# adcfft.net
KiCad netlist of a schematic drawn in EAGLE
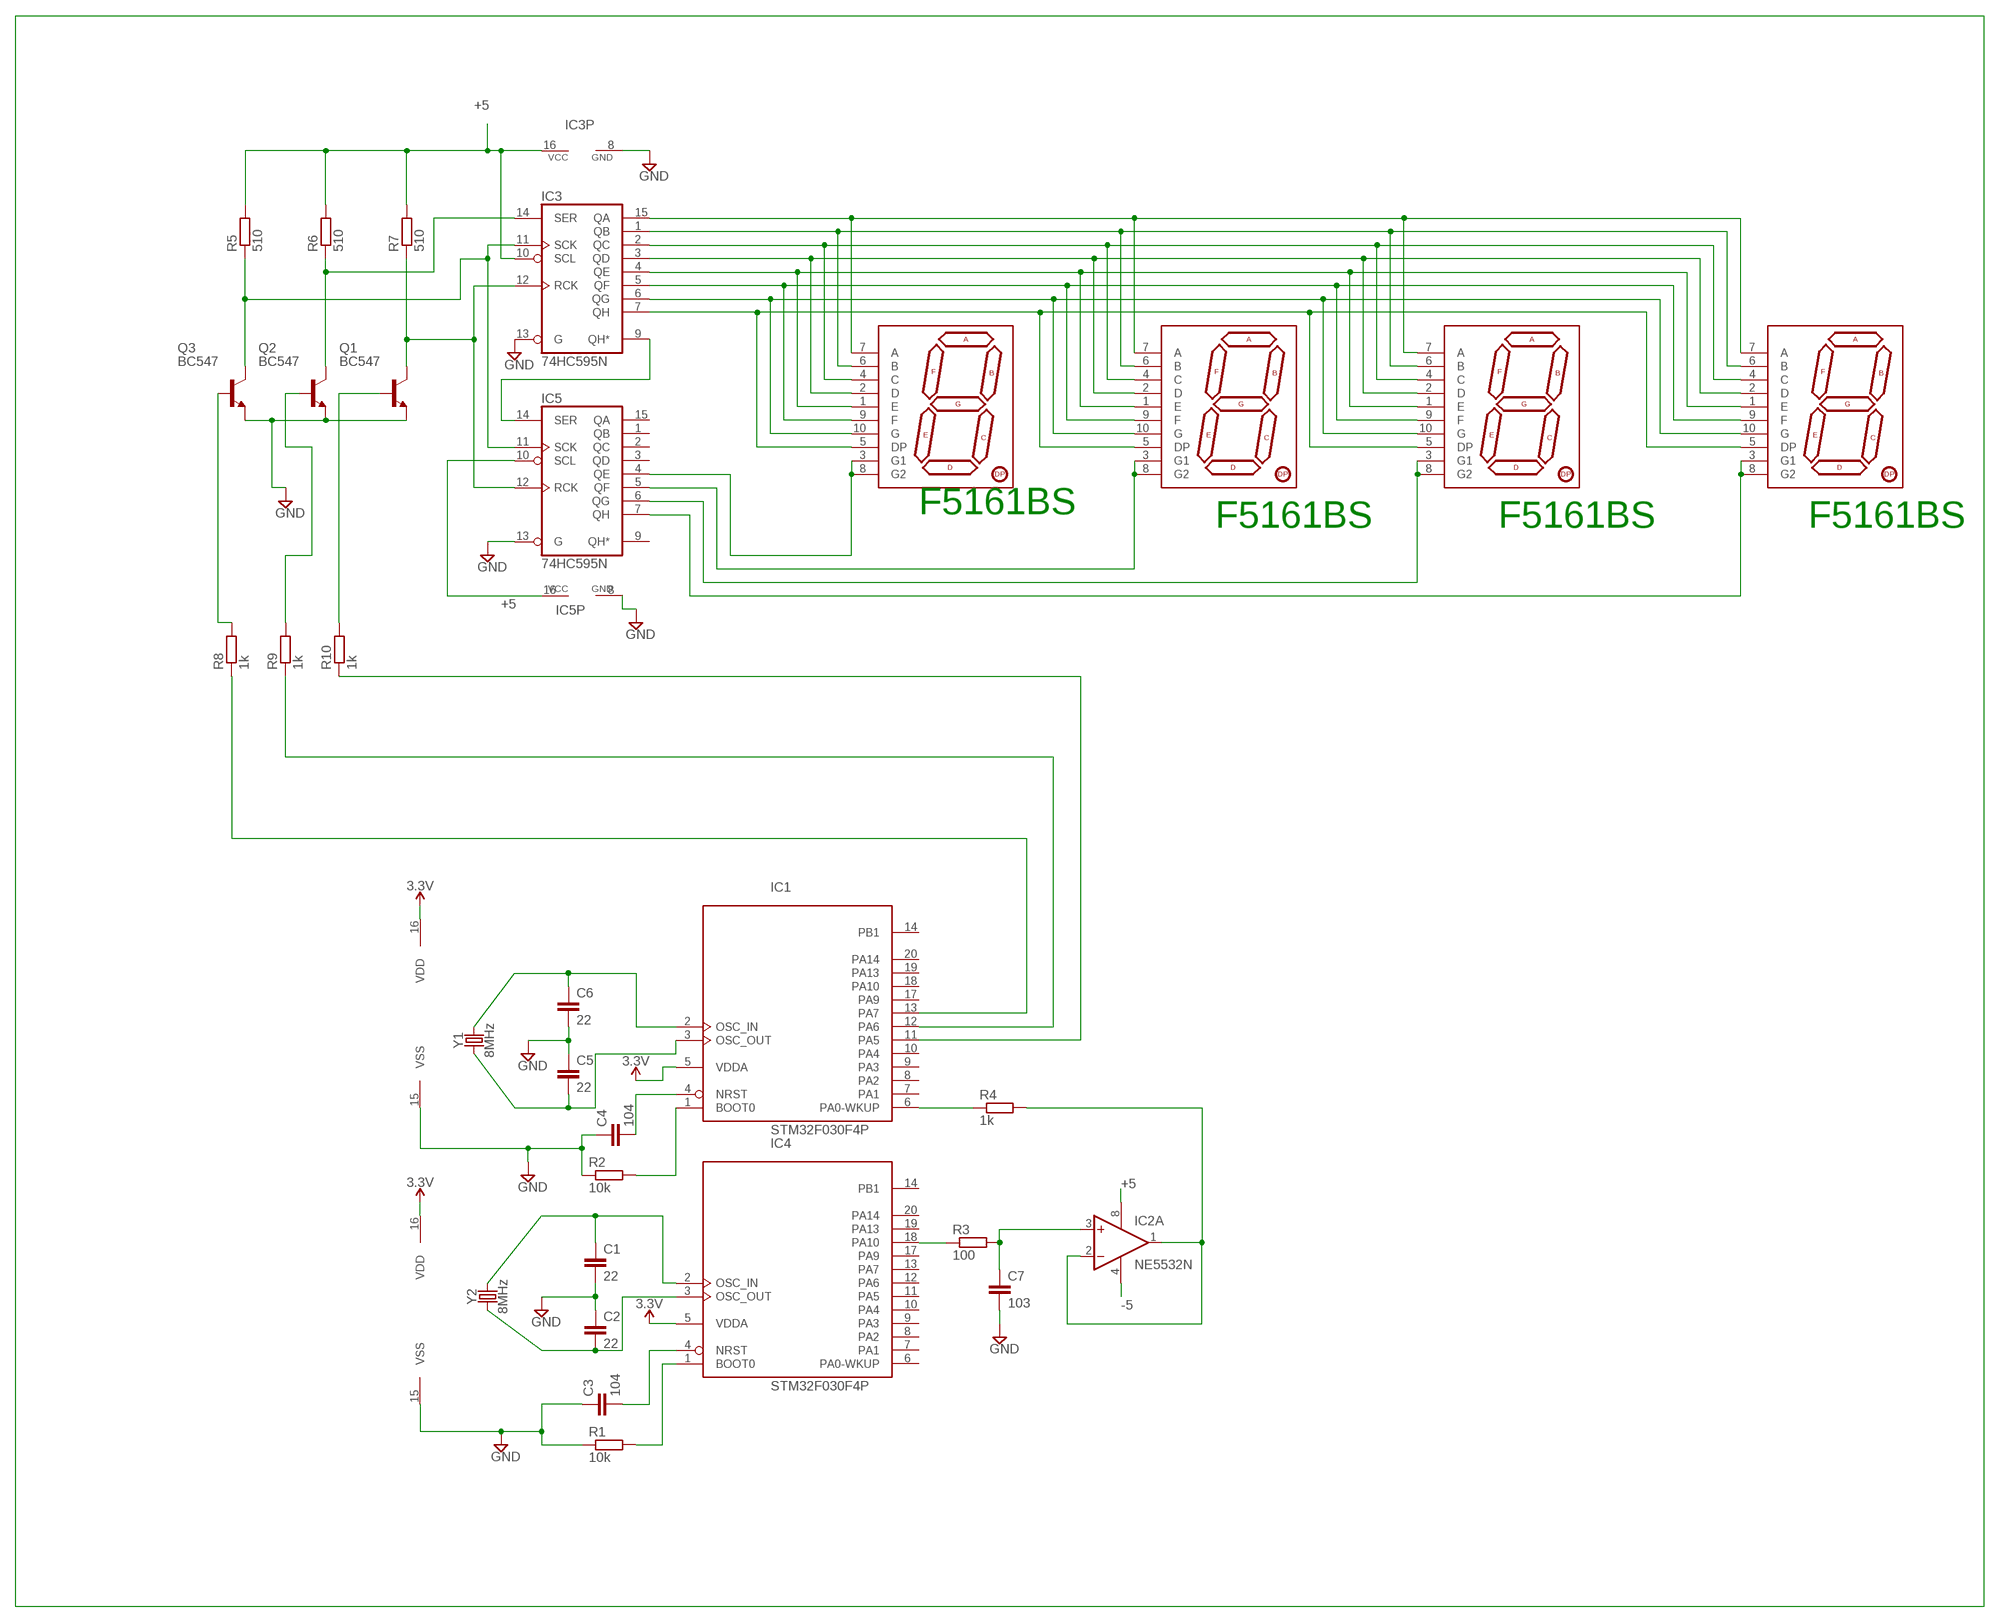
[diagram p0: schematic, sheet 1]

(export (version "E")
  (design (tool "Eeschema 10.0.6"))
  (components
    (comp (ref "C1")
      (value "22")
      (footprint "eagle-import:C0504")
      (libsource (lib "eagle-import") (part "C-EUC0504"))
    )
    (comp (ref "C2")
      (value "22")
      (footprint "eagle-import:C0504")
      (libsource (lib "eagle-import") (part "C-EUC0504"))
    )
    (comp (ref "C3")
      (value "104")
      (footprint "eagle-import:C0504")
      (libsource (lib "eagle-import") (part "C-EUC0504"))
    )
    (comp (ref "C4")
      (value "104")
      (footprint "eagle-import:C0504")
      (libsource (lib "eagle-import") (part "C-EUC0504"))
    )
    (comp (ref "C5")
      (value "22")
      (footprint "eagle-import:C0504")
      (libsource (lib "eagle-import") (part "C-EUC0504"))
    )
    (comp (ref "C6")
      (value "22")
      (footprint "eagle-import:C0504")
      (libsource (lib "eagle-import") (part "C-EUC0504"))
    )
    (comp (ref "C7")
      (value "103")
      (footprint "eagle-import:C0504")
      (libsource (lib "eagle-import") (part "C-EUC0504"))
    )
    (comp (ref "IC1")
      (value "STM32F030F4P")
      (footprint "eagle-import:TSSOP20-I")
      (libsource (lib "eagle-import") (part "STM32F030FP4"))
    )
    (comp (ref "IC2")
      (value "NE5532N")
      (footprint "eagle-import:DIL08")
      (libsource (lib "eagle-import") (part "NE5532N"))
    )
    (comp (ref "IC3")
      (value "74HC595N")
      (footprint "eagle-import:DIL16")
      (libsource (lib "eagle-import") (part "74595NHC"))
    )
    (comp (ref "IC4")
      (value "STM32F030F4P")
      (footprint "eagle-import:TSSOP20-I")
      (libsource (lib "eagle-import") (part "STM32F030FP4"))
    )
    (comp (ref "IC5")
      (value "74HC595N")
      (footprint "eagle-import:DIL16")
      (libsource (lib "eagle-import") (part "74595NHC"))
    )
    (comp (ref "Q1")
      (value "BC547")
      (footprint "eagle-import:TO92")
      (libsource (lib "eagle-import") (part "BC547"))
    )
    (comp (ref "Q2")
      (value "BC547")
      (footprint "eagle-import:TO92")
      (libsource (lib "eagle-import") (part "BC547"))
    )
    (comp (ref "Q3")
      (value "BC547")
      (footprint "eagle-import:TO92")
      (libsource (lib "eagle-import") (part "BC547"))
    )
    (comp (ref "R1")
      (value "10k")
      (footprint "eagle-import:0207_10")
      (libsource (lib "eagle-import") (part "R-EU_0207/10"))
    )
    (comp (ref "R2")
      (value "10k")
      (footprint "eagle-import:0207_10")
      (libsource (lib "eagle-import") (part "R-EU_0207/10"))
    )
    (comp (ref "R3")
      (value "100")
      (footprint "eagle-import:0207_10")
      (libsource (lib "eagle-import") (part "R-EU_0207/10"))
    )
    (comp (ref "R4")
      (value "1k")
      (footprint "eagle-import:0207_10")
      (libsource (lib "eagle-import") (part "R-EU_0207/10"))
    )
    (comp (ref "R5")
      (value "510")
      (footprint "eagle-import:0207_10")
      (libsource (lib "eagle-import") (part "R-EU_0207/10"))
    )
    (comp (ref "R6")
      (value "510")
      (footprint "eagle-import:0207_10")
      (libsource (lib "eagle-import") (part "R-EU_0207/10"))
    )
    (comp (ref "R7")
      (value "510")
      (footprint "eagle-import:0207_10")
      (libsource (lib "eagle-import") (part "R-EU_0207/10"))
    )
    (comp (ref "R8")
      (value "1k")
      (footprint "eagle-import:0207_10")
      (libsource (lib "eagle-import") (part "R-EU_0207/10"))
    )
    (comp (ref "R9")
      (value "1k")
      (footprint "eagle-import:0207_10")
      (libsource (lib "eagle-import") (part "R-EU_0207/10"))
    )
    (comp (ref "R10")
      (value "1k")
      (footprint "eagle-import:0207_10")
      (libsource (lib "eagle-import") (part "R-EU_0207/10"))
    )
    (comp (ref "U$1")
      (value "F5161BS")
      (footprint "eagle-import:7-SEGMENT-1_PTH")
      (libsource (lib "eagle-import") (part "7-SEGMENT-1DIGIT-1INCH-BLUE"))
    )
    (comp (ref "U$2")
      (value "F5161BS")
      (footprint "eagle-import:7-SEGMENT-1_PTH")
      (libsource (lib "eagle-import") (part "7-SEGMENT-1DIGIT-1INCH-BLUE"))
    )
    (comp (ref "U$3")
      (value "F5161BS")
      (footprint "eagle-import:7-SEGMENT-1_PTH")
      (libsource (lib "eagle-import") (part "7-SEGMENT-1DIGIT-1INCH-BLUE"))
    )
    (comp (ref "U$4")
      (value "F5161BS")
      (footprint "eagle-import:7-SEGMENT-1_PTH")
      (libsource (lib "eagle-import") (part "7-SEGMENT-1DIGIT-1INCH-BLUE"))
    )
    (comp (ref "Y1")
      (value "8MHz")
      (footprint "eagle-import:HC49UP")
      (libsource (lib "eagle-import") (part "CRYSTAL-8MHZSMD-HC49UP"))
    )
    (comp (ref "Y2")
      (value "8MHz")
      (footprint "eagle-import:HC49UP")
      (libsource (lib "eagle-import") (part "CRYSTAL-8MHZSMD-HC49UP"))
    )
  )
  (nets
    (net (code "1") (name "/+5") (class "Default")
      (node (ref "IC2") (pin "8") (pinfunction "V+_8") (pintype "power_in"))
      (node (ref "IC3") (pin "10") (pinfunction "SCL_10") (pintype "input"))
      (node (ref "IC3") (pin "16") (pinfunction "VCC_16") (pintype "power_in"))
      (node (ref "IC5") (pin "10") (pinfunction "SCL_10") (pintype "input"))
      (node (ref "IC5") (pin "16") (pinfunction "VCC_16") (pintype "power_in"))
      (node (ref "R5") (pin "2") (pinfunction "2_2") (pintype "passive"))
      (node (ref "R6") (pin "2") (pinfunction "2_2") (pintype "passive"))
      (node (ref "R7") (pin "2") (pinfunction "2_2") (pintype "passive"))
    )
    (net (code "2") (name "/-5") (class "Default")
      (node (ref "IC2") (pin "4") (pinfunction "V-_4") (pintype "power_in"))
    )
    (net (code "3") (name "3.3V") (class "Default")
      (node (ref "IC1") (pin "16") (pinfunction "VDD_16") (pintype "power_in"))
      (node (ref "IC1") (pin "5") (pinfunction "VDDA_5") (pintype "power_in"))
      (node (ref "IC4") (pin "16") (pinfunction "VDD_16") (pintype "power_in"))
      (node (ref "IC4") (pin "5") (pinfunction "VDDA_5") (pintype "power_in"))
    )
    (net (code "4") (name "GND") (class "Default")
      (node (ref "C1") (pin "2") (pinfunction "2_2") (pintype "passive"))
      (node (ref "C2") (pin "1") (pinfunction "1_1") (pintype "passive"))
      (node (ref "C3") (pin "1") (pinfunction "1_1") (pintype "passive"))
      (node (ref "C4") (pin "1") (pinfunction "1_1") (pintype "passive"))
      (node (ref "C5") (pin "1") (pinfunction "1_1") (pintype "passive"))
      (node (ref "C6") (pin "2") (pinfunction "2_2") (pintype "passive"))
      (node (ref "C7") (pin "2") (pinfunction "2_2") (pintype "passive"))
      (node (ref "IC1") (pin "15") (pinfunction "VSS_15") (pintype "power_in"))
      (node (ref "IC3") (pin "13") (pinfunction "G_13") (pintype "input"))
      (node (ref "IC3") (pin "8") (pinfunction "GND_8") (pintype "power_in"))
      (node (ref "IC4") (pin "15") (pinfunction "VSS_15") (pintype "power_in"))
      (node (ref "IC5") (pin "13") (pinfunction "G_13") (pintype "input"))
      (node (ref "IC5") (pin "8") (pinfunction "GND_8") (pintype "power_in"))
      (node (ref "Q1") (pin "1") (pinfunction "E_1") (pintype "passive"))
      (node (ref "Q2") (pin "1") (pinfunction "E_1") (pintype "passive"))
      (node (ref "Q3") (pin "1") (pinfunction "E_1") (pintype "passive"))
      (node (ref "R1") (pin "1") (pinfunction "1_1") (pintype "passive"))
      (node (ref "R2") (pin "1") (pinfunction "1_1") (pintype "passive"))
    )
    (net (code "5") (name "Net-(IC1A-BOOT0)") (class "Default")
      (node (ref "IC1") (pin "1") (pinfunction "BOOT0_1") (pintype "input"))
      (node (ref "R2") (pin "2") (pinfunction "2_2") (pintype "passive"))
    )
    (net (code "6") (name "Net-(IC1A-NRST)") (class "Default")
      (node (ref "C4") (pin "2") (pinfunction "2_2") (pintype "passive"))
      (node (ref "IC1") (pin "4") (pinfunction "NRST_4") (pintype "bidirectional"))
    )
    (net (code "7") (name "Net-(IC1A-OSC_IN)") (class "Default")
      (node (ref "C6") (pin "1") (pinfunction "1_1") (pintype "passive"))
      (node (ref "IC1") (pin "2") (pinfunction "OSC_IN_2") (pintype "bidirectional"))
      (node (ref "Y1") (pin "2") (pinfunction "2_2") (pintype "passive"))
    )
    (net (code "8") (name "Net-(IC1A-OSC_OUT)") (class "Default")
      (node (ref "C5") (pin "2") (pinfunction "2_2") (pintype "passive"))
      (node (ref "IC1") (pin "3") (pinfunction "OSC_OUT_3") (pintype "bidirectional"))
      (node (ref "Y1") (pin "1") (pinfunction "1_1") (pintype "passive"))
    )
    (net (code "9") (name "Net-(IC1A-PA0-WKUP)") (class "Default")
      (node (ref "IC1") (pin "6") (pinfunction "PA0-WKUP_6") (pintype "bidirectional"))
      (node (ref "R4") (pin "1") (pinfunction "1_1") (pintype "passive"))
    )
    (net (code "10") (name "Net-(IC1A-PA5)") (class "Default")
      (node (ref "IC1") (pin "11") (pinfunction "PA5_11") (pintype "bidirectional"))
      (node (ref "R10") (pin "1") (pinfunction "1_1") (pintype "passive"))
    )
    (net (code "11") (name "Net-(IC1A-PA6)") (class "Default")
      (node (ref "IC1") (pin "12") (pinfunction "PA6_12") (pintype "bidirectional"))
      (node (ref "R9") (pin "1") (pinfunction "1_1") (pintype "passive"))
    )
    (net (code "12") (name "Net-(IC1A-PA7)") (class "Default")
      (node (ref "IC1") (pin "13") (pinfunction "PA7_13") (pintype "bidirectional"))
      (node (ref "R8") (pin "1") (pinfunction "1_1") (pintype "passive"))
    )
    (net (code "13") (name "Net-(IC2A-+IN)") (class "Default")
      (node (ref "C7") (pin "1") (pinfunction "1_1") (pintype "passive"))
      (node (ref "IC2") (pin "3") (pinfunction "+IN_3") (pintype "input"))
      (node (ref "R3") (pin "2") (pinfunction "2_2") (pintype "passive"))
    )
    (net (code "14") (name "Net-(IC2A--IN)") (class "Default")
      (node (ref "IC2") (pin "1") (pinfunction "OUT_1") (pintype "output"))
      (node (ref "IC2") (pin "2") (pinfunction "-IN_2") (pintype "input"))
      (node (ref "R4") (pin "2") (pinfunction "2_2") (pintype "passive"))
    )
    (net (code "15") (name "Net-(IC3A-QA)") (class "Default")
      (node (ref "IC3") (pin "15") (pinfunction "QA_15") (pintype "tri_state"))
      (node (ref "U$1") (pin "7") (pinfunction "A_7") (pintype "bidirectional"))
      (node (ref "U$2") (pin "7") (pinfunction "A_7") (pintype "bidirectional"))
      (node (ref "U$3") (pin "7") (pinfunction "A_7") (pintype "bidirectional"))
      (node (ref "U$4") (pin "7") (pinfunction "A_7") (pintype "bidirectional"))
    )
    (net (code "16") (name "Net-(IC3A-QB)") (class "Default")
      (node (ref "IC3") (pin "1") (pinfunction "QB_1") (pintype "tri_state"))
      (node (ref "U$1") (pin "6") (pinfunction "B_6") (pintype "bidirectional"))
      (node (ref "U$2") (pin "6") (pinfunction "B_6") (pintype "bidirectional"))
      (node (ref "U$3") (pin "6") (pinfunction "B_6") (pintype "bidirectional"))
      (node (ref "U$4") (pin "6") (pinfunction "B_6") (pintype "bidirectional"))
    )
    (net (code "17") (name "Net-(IC3A-QC)") (class "Default")
      (node (ref "IC3") (pin "2") (pinfunction "QC_2") (pintype "tri_state"))
      (node (ref "U$1") (pin "4") (pinfunction "C_4") (pintype "bidirectional"))
      (node (ref "U$2") (pin "4") (pinfunction "C_4") (pintype "bidirectional"))
      (node (ref "U$3") (pin "4") (pinfunction "C_4") (pintype "bidirectional"))
      (node (ref "U$4") (pin "4") (pinfunction "C_4") (pintype "bidirectional"))
    )
    (net (code "18") (name "Net-(IC3A-QD)") (class "Default")
      (node (ref "IC3") (pin "3") (pinfunction "QD_3") (pintype "tri_state"))
      (node (ref "U$1") (pin "2") (pinfunction "D_2") (pintype "bidirectional"))
      (node (ref "U$2") (pin "2") (pinfunction "D_2") (pintype "bidirectional"))
      (node (ref "U$3") (pin "2") (pinfunction "D_2") (pintype "bidirectional"))
      (node (ref "U$4") (pin "2") (pinfunction "D_2") (pintype "bidirectional"))
    )
    (net (code "19") (name "Net-(IC3A-QE)") (class "Default")
      (node (ref "IC3") (pin "4") (pinfunction "QE_4") (pintype "tri_state"))
      (node (ref "U$1") (pin "1") (pinfunction "E_1") (pintype "bidirectional"))
      (node (ref "U$2") (pin "1") (pinfunction "E_1") (pintype "bidirectional"))
      (node (ref "U$3") (pin "1") (pinfunction "E_1") (pintype "bidirectional"))
      (node (ref "U$4") (pin "1") (pinfunction "E_1") (pintype "bidirectional"))
    )
    (net (code "20") (name "Net-(IC3A-QF)") (class "Default")
      (node (ref "IC3") (pin "5") (pinfunction "QF_5") (pintype "tri_state"))
      (node (ref "U$1") (pin "9") (pinfunction "F_9") (pintype "bidirectional"))
      (node (ref "U$2") (pin "9") (pinfunction "F_9") (pintype "bidirectional"))
      (node (ref "U$3") (pin "9") (pinfunction "F_9") (pintype "bidirectional"))
      (node (ref "U$4") (pin "9") (pinfunction "F_9") (pintype "bidirectional"))
    )
    (net (code "21") (name "Net-(IC3A-QG)") (class "Default")
      (node (ref "IC3") (pin "6") (pinfunction "QG_6") (pintype "tri_state"))
      (node (ref "U$1") (pin "10") (pinfunction "G_10") (pintype "bidirectional"))
      (node (ref "U$2") (pin "10") (pinfunction "G_10") (pintype "bidirectional"))
      (node (ref "U$3") (pin "10") (pinfunction "G_10") (pintype "bidirectional"))
      (node (ref "U$4") (pin "10") (pinfunction "G_10") (pintype "bidirectional"))
    )
    (net (code "22") (name "Net-(IC3A-QH)") (class "Default")
      (node (ref "IC3") (pin "7") (pinfunction "QH_7") (pintype "tri_state"))
      (node (ref "U$1") (pin "5") (pinfunction "DP_5") (pintype "bidirectional"))
      (node (ref "U$2") (pin "5") (pinfunction "DP_5") (pintype "bidirectional"))
      (node (ref "U$3") (pin "5") (pinfunction "DP_5") (pintype "bidirectional"))
      (node (ref "U$4") (pin "5") (pinfunction "DP_5") (pintype "bidirectional"))
    )
    (net (code "23") (name "Net-(IC3A-QH*)") (class "Default")
      (node (ref "IC3") (pin "9") (pinfunction "QH*_9") (pintype "tri_state"))
      (node (ref "IC5") (pin "14") (pinfunction "SER_14") (pintype "input"))
    )
    (net (code "24") (name "Net-(IC3A-RCK)") (class "Default")
      (node (ref "IC3") (pin "12") (pinfunction "RCK_12") (pintype "input"))
      (node (ref "IC5") (pin "12") (pinfunction "RCK_12") (pintype "input"))
      (node (ref "Q1") (pin "3") (pinfunction "C_3") (pintype "passive"))
      (node (ref "R7") (pin "1") (pinfunction "1_1") (pintype "passive"))
    )
    (net (code "25") (name "Net-(IC3A-SCK)") (class "Default")
      (node (ref "IC3") (pin "11") (pinfunction "SCK_11") (pintype "input"))
      (node (ref "IC5") (pin "11") (pinfunction "SCK_11") (pintype "input"))
      (node (ref "Q3") (pin "3") (pinfunction "C_3") (pintype "passive"))
      (node (ref "R5") (pin "1") (pinfunction "1_1") (pintype "passive"))
    )
    (net (code "26") (name "Net-(IC3A-SER)") (class "Default")
      (node (ref "IC3") (pin "14") (pinfunction "SER_14") (pintype "input"))
      (node (ref "Q2") (pin "3") (pinfunction "C_3") (pintype "passive"))
      (node (ref "R6") (pin "1") (pinfunction "1_1") (pintype "passive"))
    )
    (net (code "27") (name "Net-(IC4A-BOOT0)") (class "Default")
      (node (ref "IC4") (pin "1") (pinfunction "BOOT0_1") (pintype "input"))
      (node (ref "R1") (pin "2") (pinfunction "2_2") (pintype "passive"))
    )
    (net (code "28") (name "Net-(IC4A-NRST)") (class "Default")
      (node (ref "C3") (pin "2") (pinfunction "2_2") (pintype "passive"))
      (node (ref "IC4") (pin "4") (pinfunction "NRST_4") (pintype "bidirectional"))
    )
    (net (code "29") (name "Net-(IC4A-OSC_IN)") (class "Default")
      (node (ref "C1") (pin "1") (pinfunction "1_1") (pintype "passive"))
      (node (ref "IC4") (pin "2") (pinfunction "OSC_IN_2") (pintype "bidirectional"))
      (node (ref "Y2") (pin "2") (pinfunction "2_2") (pintype "passive"))
    )
    (net (code "30") (name "Net-(IC4A-OSC_OUT)") (class "Default")
      (node (ref "C2") (pin "2") (pinfunction "2_2") (pintype "passive"))
      (node (ref "IC4") (pin "3") (pinfunction "OSC_OUT_3") (pintype "bidirectional"))
      (node (ref "Y2") (pin "1") (pinfunction "1_1") (pintype "passive"))
    )
    (net (code "31") (name "Net-(IC4A-PA10)") (class "Default")
      (node (ref "IC4") (pin "18") (pinfunction "PA10_18") (pintype "bidirectional"))
      (node (ref "R3") (pin "1") (pinfunction "1_1") (pintype "passive"))
    )
    (net (code "32") (name "Net-(IC5A-QE)") (class "Default")
      (node (ref "IC5") (pin "4") (pinfunction "QE_4") (pintype "tri_state"))
      (node (ref "U$1") (pin "3") (pinfunction "G1_3") (pintype "bidirectional"))
      (node (ref "U$1") (pin "8") (pinfunction "G2_8") (pintype "bidirectional"))
    )
    (net (code "33") (name "Net-(IC5A-QF)") (class "Default")
      (node (ref "IC5") (pin "5") (pinfunction "QF_5") (pintype "tri_state"))
      (node (ref "U$2") (pin "3") (pinfunction "G1_3") (pintype "bidirectional"))
      (node (ref "U$2") (pin "8") (pinfunction "G2_8") (pintype "bidirectional"))
    )
    (net (code "34") (name "Net-(IC5A-QG)") (class "Default")
      (node (ref "IC5") (pin "6") (pinfunction "QG_6") (pintype "tri_state"))
      (node (ref "U$3") (pin "3") (pinfunction "G1_3") (pintype "bidirectional"))
      (node (ref "U$3") (pin "8") (pinfunction "G2_8") (pintype "bidirectional"))
    )
    (net (code "35") (name "Net-(IC5A-QH)") (class "Default")
      (node (ref "IC5") (pin "7") (pinfunction "QH_7") (pintype "tri_state"))
      (node (ref "U$4") (pin "3") (pinfunction "G1_3") (pintype "bidirectional"))
      (node (ref "U$4") (pin "8") (pinfunction "G2_8") (pintype "bidirectional"))
    )
    (net (code "36") (name "Net-(Q1-B)") (class "Default")
      (node (ref "Q1") (pin "2") (pinfunction "B_2") (pintype "passive"))
      (node (ref "R10") (pin "2") (pinfunction "2_2") (pintype "passive"))
    )
    (net (code "37") (name "Net-(Q2-B)") (class "Default")
      (node (ref "Q2") (pin "2") (pinfunction "B_2") (pintype "passive"))
      (node (ref "R9") (pin "2") (pinfunction "2_2") (pintype "passive"))
    )
    (net (code "38") (name "Net-(Q3-B)") (class "Default")
      (node (ref "Q3") (pin "2") (pinfunction "B_2") (pintype "passive"))
      (node (ref "R8") (pin "2") (pinfunction "2_2") (pintype "passive"))
    )
    (net (code "39") (name "unconnected-(IC1A-PA1-Pad7)") (class "Default")
      (node (ref "IC1") (pin "7") (pinfunction "PA1_7") (pintype "bidirectional"))
    )
    (net (code "40") (name "unconnected-(IC1A-PA2-Pad8)") (class "Default")
      (node (ref "IC1") (pin "8") (pinfunction "PA2_8") (pintype "bidirectional"))
    )
    (net (code "41") (name "unconnected-(IC1A-PA3-Pad9)") (class "Default")
      (node (ref "IC1") (pin "9") (pinfunction "PA3_9") (pintype "bidirectional"))
    )
    (net (code "42") (name "unconnected-(IC1A-PA4-Pad10)") (class "Default")
      (node (ref "IC1") (pin "10") (pinfunction "PA4_10") (pintype "bidirectional"))
    )
    (net (code "43") (name "unconnected-(IC1A-PA9-Pad17)") (class "Default")
      (node (ref "IC1") (pin "17") (pinfunction "PA9_17") (pintype "bidirectional"))
    )
    (net (code "44") (name "unconnected-(IC1A-PA10-Pad18)") (class "Default")
      (node (ref "IC1") (pin "18") (pinfunction "PA10_18") (pintype "bidirectional"))
    )
    (net (code "45") (name "unconnected-(IC1A-PA13-Pad19)") (class "Default")
      (node (ref "IC1") (pin "19") (pinfunction "PA13_19") (pintype "bidirectional"))
    )
    (net (code "46") (name "unconnected-(IC1A-PA14-Pad20)") (class "Default")
      (node (ref "IC1") (pin "20") (pinfunction "PA14_20") (pintype "bidirectional"))
    )
    (net (code "47") (name "unconnected-(IC1A-PB1-Pad14)") (class "Default")
      (node (ref "IC1") (pin "14") (pinfunction "PB1_14") (pintype "bidirectional"))
    )
    (net (code "48") (name "unconnected-(IC4A-PA0-WKUP-Pad6)") (class "Default")
      (node (ref "IC4") (pin "6") (pinfunction "PA0-WKUP_6") (pintype "bidirectional"))
    )
    (net (code "49") (name "unconnected-(IC4A-PA1-Pad7)") (class "Default")
      (node (ref "IC4") (pin "7") (pinfunction "PA1_7") (pintype "bidirectional"))
    )
    (net (code "50") (name "unconnected-(IC4A-PA2-Pad8)") (class "Default")
      (node (ref "IC4") (pin "8") (pinfunction "PA2_8") (pintype "bidirectional"))
    )
    (net (code "51") (name "unconnected-(IC4A-PA3-Pad9)") (class "Default")
      (node (ref "IC4") (pin "9") (pinfunction "PA3_9") (pintype "bidirectional"))
    )
    (net (code "52") (name "unconnected-(IC4A-PA4-Pad10)") (class "Default")
      (node (ref "IC4") (pin "10") (pinfunction "PA4_10") (pintype "bidirectional"))
    )
    (net (code "53") (name "unconnected-(IC4A-PA5-Pad11)") (class "Default")
      (node (ref "IC4") (pin "11") (pinfunction "PA5_11") (pintype "bidirectional"))
    )
    (net (code "54") (name "unconnected-(IC4A-PA6-Pad12)") (class "Default")
      (node (ref "IC4") (pin "12") (pinfunction "PA6_12") (pintype "bidirectional"))
    )
    (net (code "55") (name "unconnected-(IC4A-PA7-Pad13)") (class "Default")
      (node (ref "IC4") (pin "13") (pinfunction "PA7_13") (pintype "bidirectional"))
    )
    (net (code "56") (name "unconnected-(IC4A-PA9-Pad17)") (class "Default")
      (node (ref "IC4") (pin "17") (pinfunction "PA9_17") (pintype "bidirectional"))
    )
    (net (code "57") (name "unconnected-(IC4A-PA13-Pad19)") (class "Default")
      (node (ref "IC4") (pin "19") (pinfunction "PA13_19") (pintype "bidirectional"))
    )
    (net (code "58") (name "unconnected-(IC4A-PA14-Pad20)") (class "Default")
      (node (ref "IC4") (pin "20") (pinfunction "PA14_20") (pintype "bidirectional"))
    )
    (net (code "59") (name "unconnected-(IC4A-PB1-Pad14)") (class "Default")
      (node (ref "IC4") (pin "14") (pinfunction "PB1_14") (pintype "bidirectional"))
    )
    (net (code "60") (name "unconnected-(IC5A-QA-Pad15)") (class "Default")
      (node (ref "IC5") (pin "15") (pinfunction "QA_15") (pintype "tri_state"))
    )
    (net (code "61") (name "unconnected-(IC5A-QB-Pad1)") (class "Default")
      (node (ref "IC5") (pin "1") (pinfunction "QB_1") (pintype "tri_state"))
    )
    (net (code "62") (name "unconnected-(IC5A-QC-Pad2)") (class "Default")
      (node (ref "IC5") (pin "2") (pinfunction "QC_2") (pintype "tri_state"))
    )
    (net (code "63") (name "unconnected-(IC5A-QD-Pad3)") (class "Default")
      (node (ref "IC5") (pin "3") (pinfunction "QD_3") (pintype "tri_state"))
    )
    (net (code "64") (name "unconnected-(IC5A-QH*-Pad9)") (class "Default")
      (node (ref "IC5") (pin "9") (pinfunction "QH*_9") (pintype "tri_state"))
    )
  )
)
